# reg_board.net
KiCad netlist of a schematic drawn in EAGLE
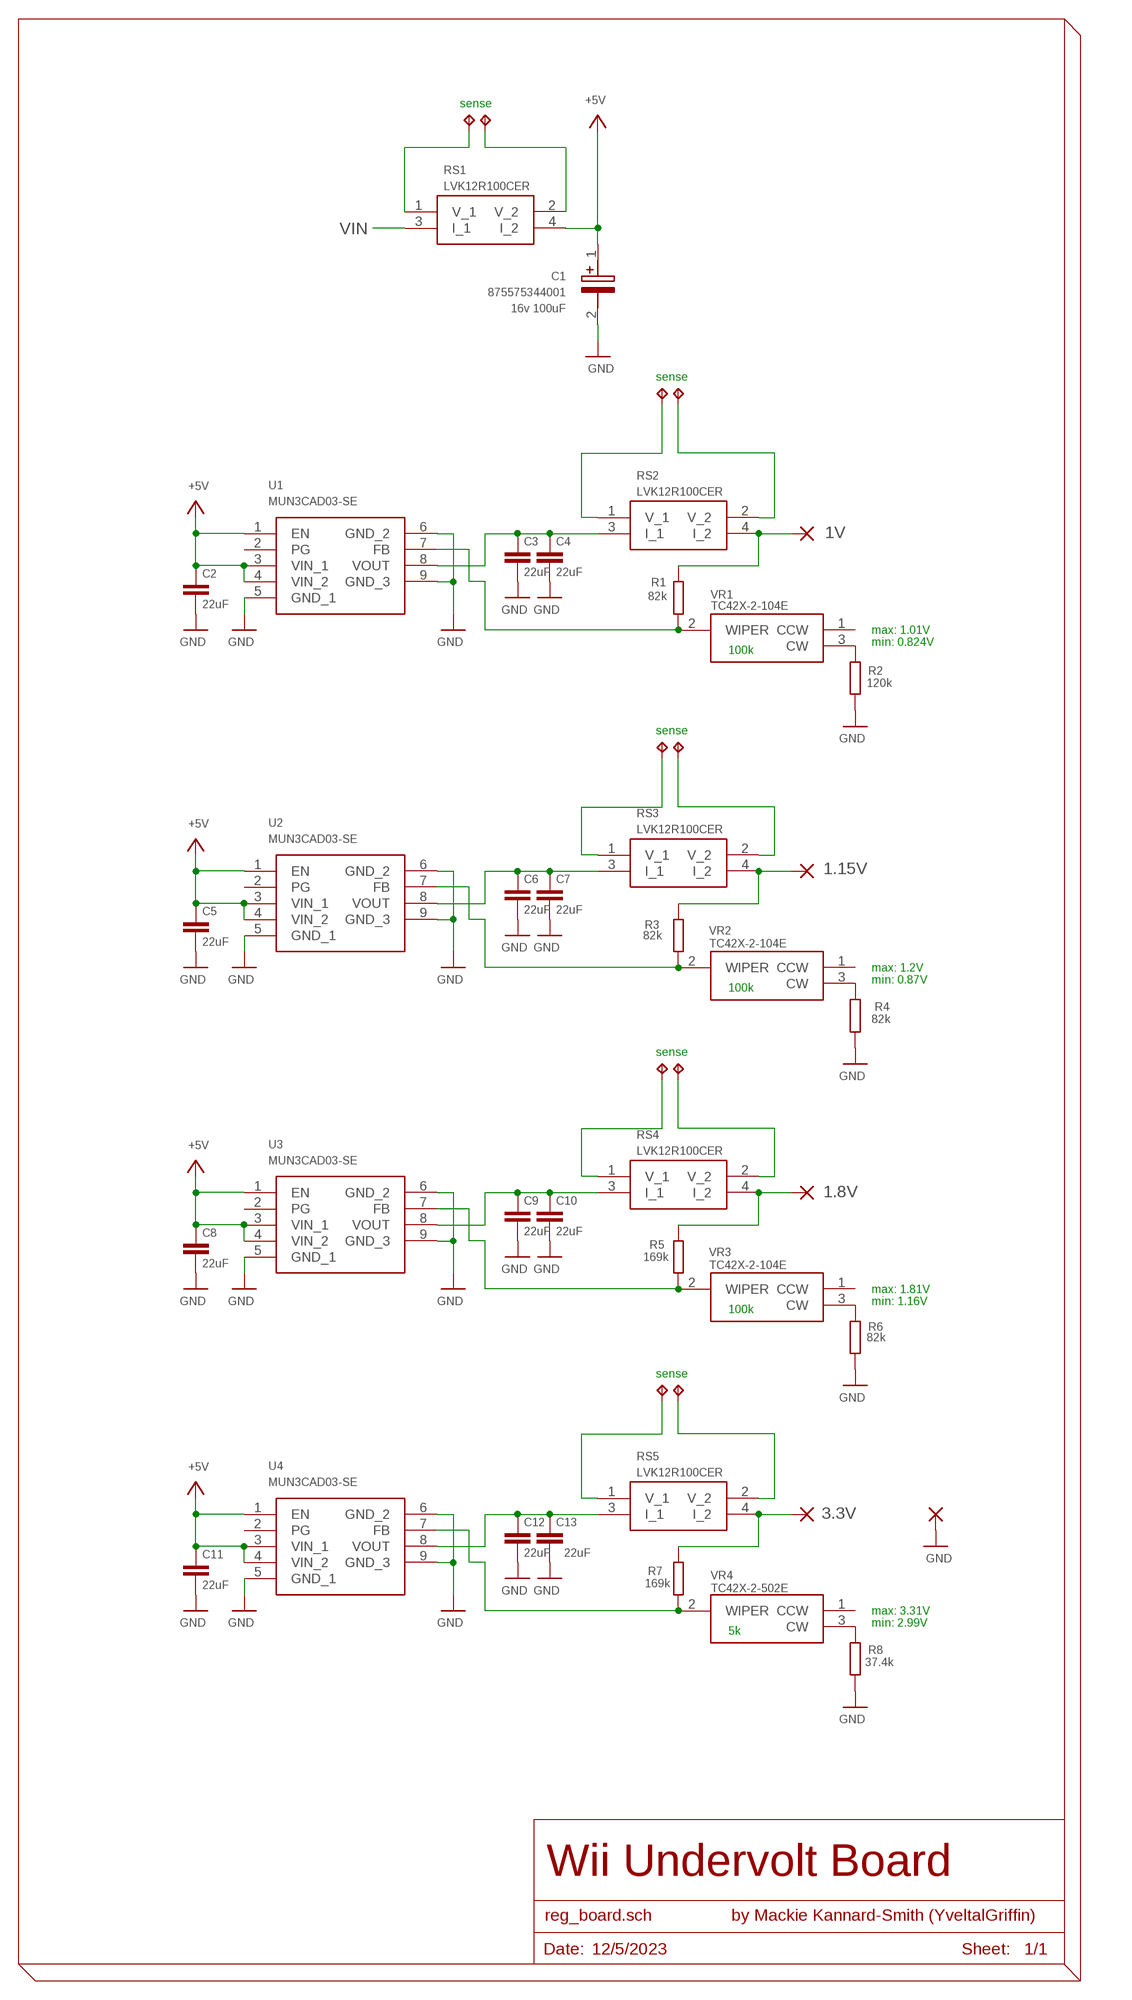
[diagram p0: schematic, sheet 1]

(export (version "E")
  (design (tool "Eeschema 10.0.6"))
  (components
    (comp (ref "C1")
      (value "875575344001")
      (footprint "eagle-import:CAPAE660X610N")
      (libsource (lib "eagle-import") (part "875575344001"))
    )
    (comp (ref "C2")
      (value "22uF")
      (footprint "eagle-import:C0603")
      (libsource (lib "eagle-import") (part "C-USC0603"))
    )
    (comp (ref "C3")
      (value "22uF")
      (footprint "eagle-import:C0603")
      (libsource (lib "eagle-import") (part "C-USC0603"))
    )
    (comp (ref "C4")
      (value "22uF")
      (footprint "eagle-import:C0603")
      (libsource (lib "eagle-import") (part "C-USC0603"))
    )
    (comp (ref "C5")
      (value "22uF")
      (footprint "eagle-import:C0603")
      (libsource (lib "eagle-import") (part "C-USC0603"))
    )
    (comp (ref "C6")
      (value "22uF")
      (footprint "eagle-import:C0603")
      (libsource (lib "eagle-import") (part "C-USC0603"))
    )
    (comp (ref "C7")
      (value "22uF")
      (footprint "eagle-import:C0603")
      (libsource (lib "eagle-import") (part "C-USC0603"))
    )
    (comp (ref "C8")
      (value "22uF")
      (footprint "eagle-import:C0603")
      (libsource (lib "eagle-import") (part "C-USC0603"))
    )
    (comp (ref "C9")
      (value "22uF")
      (footprint "eagle-import:C0603")
      (libsource (lib "eagle-import") (part "C-USC0603"))
    )
    (comp (ref "C10")
      (value "22uF")
      (footprint "eagle-import:C0603")
      (libsource (lib "eagle-import") (part "C-USC0603"))
    )
    (comp (ref "C11")
      (value "22uF")
      (footprint "eagle-import:C0603")
      (libsource (lib "eagle-import") (part "C-USC0603"))
    )
    (comp (ref "C12")
      (value "22uF")
      (footprint "eagle-import:C0603")
      (libsource (lib "eagle-import") (part "C-USC0603"))
    )
    (comp (ref "C13")
      (value "22uF")
      (footprint "eagle-import:C0603")
      (libsource (lib "eagle-import") (part "C-USC0603"))
    )
    (comp (ref "PAD1")
      (value "SMD5")
      (footprint "eagle-import:SMD2,54-5,08")
      (libsource (lib "eagle-import") (part "SMD5"))
    )
    (comp (ref "PAD2")
      (value "SMD5")
      (footprint "eagle-import:SMD2,54-5,08")
      (libsource (lib "eagle-import") (part "SMD5"))
    )
    (comp (ref "PAD3")
      (value "SMD5")
      (footprint "eagle-import:SMD2,54-5,08")
      (libsource (lib "eagle-import") (part "SMD5"))
    )
    (comp (ref "PAD4")
      (value "SMD5")
      (footprint "eagle-import:SMD2,54-5,08")
      (libsource (lib "eagle-import") (part "SMD5"))
    )
    (comp (ref "PAD5")
      (value "SMD5")
      (footprint "eagle-import:SMD2,54-5,08")
      (libsource (lib "eagle-import") (part "SMD5"))
    )
    (comp (ref "R1")
      (value "82k")
      (footprint "eagle-import:R0402")
      (libsource (lib "eagle-import") (part "R-US_R0402"))
    )
    (comp (ref "R2")
      (value "120k")
      (footprint "eagle-import:R0402")
      (libsource (lib "eagle-import") (part "R-US_R0402"))
    )
    (comp (ref "R3")
      (value "82k")
      (footprint "eagle-import:R0402")
      (libsource (lib "eagle-import") (part "R-US_R0402"))
    )
    (comp (ref "R4")
      (value "82k")
      (footprint "eagle-import:R0402")
      (libsource (lib "eagle-import") (part "R-US_R0402"))
    )
    (comp (ref "R5")
      (value "169k")
      (footprint "eagle-import:R0402")
      (libsource (lib "eagle-import") (part "R-US_R0402"))
    )
    (comp (ref "R6")
      (value "82k")
      (footprint "eagle-import:R0402")
      (libsource (lib "eagle-import") (part "R-US_R0402"))
    )
    (comp (ref "R7")
      (value "169k")
      (footprint "eagle-import:R0402")
      (libsource (lib "eagle-import") (part "R-US_R0402"))
    )
    (comp (ref "R8")
      (value "37.4k")
      (footprint "eagle-import:R0402")
      (libsource (lib "eagle-import") (part "R-US_R0402"))
    )
    (comp (ref "RS1")
      (value "LVK12R100CER")
      (footprint "eagle-import:LVK12R100CER")
      (fields (field (name "MOUSER_PART_NUMBER") "588-LVK12R100CER"))
      (libsource (lib "eagle-import") (part "LVK12R100CER"))
    )
    (comp (ref "RS2")
      (value "LVK12R100CER")
      (footprint "eagle-import:LVK12R100CER")
      (fields (field (name "MOUSER_PART_NUMBER") "588-LVK12R100CER"))
      (libsource (lib "eagle-import") (part "LVK12R100CER"))
    )
    (comp (ref "RS3")
      (value "LVK12R100CER")
      (footprint "eagle-import:LVK12R100CER")
      (fields (field (name "MOUSER_PART_NUMBER") "588-LVK12R100CER"))
      (libsource (lib "eagle-import") (part "LVK12R100CER"))
    )
    (comp (ref "RS4")
      (value "LVK12R100CER")
      (footprint "eagle-import:LVK12R100CER")
      (fields (field (name "MOUSER_PART_NUMBER") "588-LVK12R100CER"))
      (libsource (lib "eagle-import") (part "LVK12R100CER"))
    )
    (comp (ref "RS5")
      (value "LVK12R100CER")
      (footprint "eagle-import:LVK12R100CER")
      (fields (field (name "MOUSER_PART_NUMBER") "588-LVK12R100CER"))
      (libsource (lib "eagle-import") (part "LVK12R100CER"))
    )
    (comp (ref "TP1")
      (value "TPTP08R")
      (footprint "eagle-import:TP08R")
      (libsource (lib "eagle-import") (part "TPTP08R"))
    )
    (comp (ref "TP2")
      (value "TPTP08R")
      (footprint "eagle-import:TP08R")
      (libsource (lib "eagle-import") (part "TPTP08R"))
    )
    (comp (ref "TP3")
      (value "TPTP08R")
      (footprint "eagle-import:TP08R")
      (libsource (lib "eagle-import") (part "TPTP08R"))
    )
    (comp (ref "TP4")
      (value "TPTP08R")
      (footprint "eagle-import:TP08R")
      (libsource (lib "eagle-import") (part "TPTP08R"))
    )
    (comp (ref "TP5")
      (value "TPTP08R")
      (footprint "eagle-import:TP08R")
      (libsource (lib "eagle-import") (part "TPTP08R"))
    )
    (comp (ref "TP6")
      (value "TPTP08R")
      (footprint "eagle-import:TP08R")
      (libsource (lib "eagle-import") (part "TPTP08R"))
    )
    (comp (ref "TP7")
      (value "TPTP08R")
      (footprint "eagle-import:TP08R")
      (libsource (lib "eagle-import") (part "TPTP08R"))
    )
    (comp (ref "TP8")
      (value "TPTP08R")
      (footprint "eagle-import:TP08R")
      (libsource (lib "eagle-import") (part "TPTP08R"))
    )
    (comp (ref "TP9")
      (value "TPTP08R")
      (footprint "eagle-import:TP08R")
      (libsource (lib "eagle-import") (part "TPTP08R"))
    )
    (comp (ref "TP10")
      (value "TPTP08R")
      (footprint "eagle-import:TP08R")
      (libsource (lib "eagle-import") (part "TPTP08R"))
    )
    (comp (ref "U1")
      (value "MUN3CAD03-SE")
      (footprint "eagle-import:MUN3CAD03SE")
      (fields (field (name "MOUSER_PART_NUMBER") "108-MUN3CAD03-SE"))
      (libsource (lib "eagle-import") (part "MUN3CAD03-SE"))
    )
    (comp (ref "U2")
      (value "MUN3CAD03-SE")
      (footprint "eagle-import:MUN3CAD03SE")
      (fields (field (name "MOUSER_PART_NUMBER") "108-MUN3CAD03-SE"))
      (libsource (lib "eagle-import") (part "MUN3CAD03-SE"))
    )
    (comp (ref "U3")
      (value "MUN3CAD03-SE")
      (footprint "eagle-import:MUN3CAD03SE")
      (fields (field (name "MOUSER_PART_NUMBER") "108-MUN3CAD03-SE"))
      (libsource (lib "eagle-import") (part "MUN3CAD03-SE"))
    )
    (comp (ref "U4")
      (value "MUN3CAD03-SE")
      (footprint "eagle-import:MUN3CAD03SE")
      (fields (field (name "MOUSER_PART_NUMBER") "108-MUN3CAD03-SE"))
      (libsource (lib "eagle-import") (part "MUN3CAD03-SE"))
    )
    (comp (ref "VR1")
      (value "TC42X-2-104E")
      (footprint "eagle-import:TC42X2103E")
      (fields (field (name "MOUSER_PART_NUMBER") "652-TC42X-2-104E"))
      (libsource (lib "eagle-import") (part "TC42X-2-104E"))
    )
    (comp (ref "VR2")
      (value "TC42X-2-104E")
      (footprint "eagle-import:TC42X2103E")
      (fields (field (name "MOUSER_PART_NUMBER") "652-TC42X-2-104E"))
      (libsource (lib "eagle-import") (part "TC42X-2-104E"))
    )
    (comp (ref "VR3")
      (value "TC42X-2-104E")
      (footprint "eagle-import:TC42X2103E")
      (fields (field (name "MOUSER_PART_NUMBER") "652-TC42X-2-104E"))
      (libsource (lib "eagle-import") (part "TC42X-2-104E"))
    )
    (comp (ref "VR4")
      (value "TC42X-2-502E")
      (footprint "eagle-import:TC42X2103E")
      (fields
        (field (name "MANUFACTURER_PART_NUMBER") "TC42X-2-104E")
        (field (name "MOUSER_PART_NUMBER") "652-TC42X-2-104E")
      )
      (libsource (lib "eagle-import") (part "TC42X-2-104E"))
    )
  )
  (nets
    (net (code "1") (name "+5V") (class "Default")
      (node (ref "C1") (pin "1") (pinfunction "+_1") (pintype "bidirectional"))
      (node (ref "C11") (pin "1") (pinfunction "1_1") (pintype "passive"))
      (node (ref "C2") (pin "1") (pinfunction "1_1") (pintype "passive"))
      (node (ref "C5") (pin "1") (pinfunction "1_1") (pintype "passive"))
      (node (ref "C8") (pin "1") (pinfunction "1_1") (pintype "passive"))
      (node (ref "RS1") (pin "4") (pinfunction "I_2_4") (pintype "bidirectional"))
      (node (ref "U1") (pin "1") (pinfunction "EN_1") (pintype "bidirectional"))
      (node (ref "U1") (pin "3") (pinfunction "VIN_1_3") (pintype "bidirectional"))
      (node (ref "U1") (pin "4") (pinfunction "VIN_2_4") (pintype "bidirectional"))
      (node (ref "U2") (pin "1") (pinfunction "EN_1") (pintype "bidirectional"))
      (node (ref "U2") (pin "3") (pinfunction "VIN_1_3") (pintype "bidirectional"))
      (node (ref "U2") (pin "4") (pinfunction "VIN_2_4") (pintype "bidirectional"))
      (node (ref "U3") (pin "1") (pinfunction "EN_1") (pintype "bidirectional"))
      (node (ref "U3") (pin "3") (pinfunction "VIN_1_3") (pintype "bidirectional"))
      (node (ref "U3") (pin "4") (pinfunction "VIN_2_4") (pintype "bidirectional"))
      (node (ref "U4") (pin "1") (pinfunction "EN_1") (pintype "bidirectional"))
      (node (ref "U4") (pin "3") (pinfunction "VIN_1_3") (pintype "bidirectional"))
      (node (ref "U4") (pin "4") (pinfunction "VIN_2_4") (pintype "bidirectional"))
    )
    (net (code "2") (name "/1.8V") (class "Default")
      (node (ref "PAD4") (pin "1") (pinfunction "P_1") (pintype "passive"))
      (node (ref "R5") (pin "2") (pinfunction "2_2") (pintype "passive"))
      (node (ref "RS4") (pin "4") (pinfunction "I_2_4") (pintype "bidirectional"))
    )
    (net (code "3") (name "/1.15V") (class "Default")
      (node (ref "PAD3") (pin "1") (pinfunction "P_1") (pintype "passive"))
      (node (ref "R3") (pin "2") (pinfunction "2_2") (pintype "passive"))
      (node (ref "RS3") (pin "4") (pinfunction "I_2_4") (pintype "bidirectional"))
    )
    (net (code "4") (name "/1V") (class "Default")
      (node (ref "PAD1") (pin "1") (pinfunction "P_1") (pintype "passive"))
      (node (ref "R1") (pin "2") (pinfunction "2_2") (pintype "passive"))
      (node (ref "RS2") (pin "4") (pinfunction "I_2_4") (pintype "bidirectional"))
    )
    (net (code "5") (name "/3.3V") (class "Default")
      (node (ref "PAD5") (pin "1") (pinfunction "P_1") (pintype "passive"))
      (node (ref "R7") (pin "2") (pinfunction "2_2") (pintype "passive"))
      (node (ref "RS5") (pin "4") (pinfunction "I_2_4") (pintype "bidirectional"))
    )
    (net (code "6") (name "/VIN") (class "Default")
      (node (ref "RS1") (pin "3") (pinfunction "I_1_3") (pintype "bidirectional"))
    )
    (net (code "7") (name "GND") (class "Default")
      (node (ref "C1") (pin "2") (pinfunction "-_2") (pintype "bidirectional"))
      (node (ref "C10") (pin "2") (pinfunction "2_2") (pintype "passive"))
      (node (ref "C11") (pin "2") (pinfunction "2_2") (pintype "passive"))
      (node (ref "C12") (pin "2") (pinfunction "2_2") (pintype "passive"))
      (node (ref "C13") (pin "2") (pinfunction "2_2") (pintype "passive"))
      (node (ref "C2") (pin "2") (pinfunction "2_2") (pintype "passive"))
      (node (ref "C3") (pin "2") (pinfunction "2_2") (pintype "passive"))
      (node (ref "C4") (pin "2") (pinfunction "2_2") (pintype "passive"))
      (node (ref "C5") (pin "2") (pinfunction "2_2") (pintype "passive"))
      (node (ref "C6") (pin "2") (pinfunction "2_2") (pintype "passive"))
      (node (ref "C7") (pin "2") (pinfunction "2_2") (pintype "passive"))
      (node (ref "C8") (pin "2") (pinfunction "2_2") (pintype "passive"))
      (node (ref "C9") (pin "2") (pinfunction "2_2") (pintype "passive"))
      (node (ref "PAD2") (pin "1") (pinfunction "P_1") (pintype "passive"))
      (node (ref "R2") (pin "1") (pinfunction "1_1") (pintype "passive"))
      (node (ref "R4") (pin "1") (pinfunction "1_1") (pintype "passive"))
      (node (ref "R6") (pin "1") (pinfunction "1_1") (pintype "passive"))
      (node (ref "R8") (pin "1") (pinfunction "1_1") (pintype "passive"))
      (node (ref "U1") (pin "5") (pinfunction "GND_1_5") (pintype "bidirectional"))
      (node (ref "U1") (pin "6") (pinfunction "GND_2_6") (pintype "bidirectional"))
      (node (ref "U1") (pin "9") (pinfunction "GND_3_9") (pintype "bidirectional"))
      (node (ref "U2") (pin "5") (pinfunction "GND_1_5") (pintype "bidirectional"))
      (node (ref "U2") (pin "6") (pinfunction "GND_2_6") (pintype "bidirectional"))
      (node (ref "U2") (pin "9") (pinfunction "GND_3_9") (pintype "bidirectional"))
      (node (ref "U3") (pin "5") (pinfunction "GND_1_5") (pintype "bidirectional"))
      (node (ref "U3") (pin "6") (pinfunction "GND_2_6") (pintype "bidirectional"))
      (node (ref "U3") (pin "9") (pinfunction "GND_3_9") (pintype "bidirectional"))
      (node (ref "U4") (pin "5") (pinfunction "GND_1_5") (pintype "bidirectional"))
      (node (ref "U4") (pin "6") (pinfunction "GND_2_6") (pintype "bidirectional"))
      (node (ref "U4") (pin "9") (pinfunction "GND_3_9") (pintype "bidirectional"))
    )
    (net (code "8") (name "Net-(RS1-V_1)") (class "Default")
      (node (ref "RS1") (pin "1") (pinfunction "V_1_1") (pintype "bidirectional"))
      (node (ref "TP4") (pin "TP") (pinfunction "TP_TP") (pintype "input"))
    )
    (net (code "9") (name "Net-(RS1-V_2)") (class "Default")
      (node (ref "RS1") (pin "2") (pinfunction "V_2_2") (pintype "bidirectional"))
      (node (ref "TP3") (pin "TP") (pinfunction "TP_TP") (pintype "input"))
    )
    (net (code "10") (name "Net-(RS2-I_1)") (class "Default")
      (node (ref "C3") (pin "1") (pinfunction "1_1") (pintype "passive"))
      (node (ref "C4") (pin "1") (pinfunction "1_1") (pintype "passive"))
      (node (ref "RS2") (pin "3") (pinfunction "I_1_3") (pintype "bidirectional"))
      (node (ref "U1") (pin "8") (pinfunction "VOUT_8") (pintype "bidirectional"))
    )
    (net (code "11") (name "Net-(RS2-V_1)") (class "Default")
      (node (ref "RS2") (pin "1") (pinfunction "V_1_1") (pintype "bidirectional"))
      (node (ref "TP1") (pin "TP") (pinfunction "TP_TP") (pintype "input"))
    )
    (net (code "12") (name "Net-(RS2-V_2)") (class "Default")
      (node (ref "RS2") (pin "2") (pinfunction "V_2_2") (pintype "bidirectional"))
      (node (ref "TP2") (pin "TP") (pinfunction "TP_TP") (pintype "input"))
    )
    (net (code "13") (name "Net-(RS3-I_1)") (class "Default")
      (node (ref "C6") (pin "1") (pinfunction "1_1") (pintype "passive"))
      (node (ref "C7") (pin "1") (pinfunction "1_1") (pintype "passive"))
      (node (ref "RS3") (pin "3") (pinfunction "I_1_3") (pintype "bidirectional"))
      (node (ref "U2") (pin "8") (pinfunction "VOUT_8") (pintype "bidirectional"))
    )
    (net (code "14") (name "Net-(RS3-V_1)") (class "Default")
      (node (ref "RS3") (pin "1") (pinfunction "V_1_1") (pintype "bidirectional"))
      (node (ref "TP5") (pin "TP") (pinfunction "TP_TP") (pintype "input"))
    )
    (net (code "15") (name "Net-(RS3-V_2)") (class "Default")
      (node (ref "RS3") (pin "2") (pinfunction "V_2_2") (pintype "bidirectional"))
      (node (ref "TP6") (pin "TP") (pinfunction "TP_TP") (pintype "input"))
    )
    (net (code "16") (name "Net-(RS4-I_1)") (class "Default")
      (node (ref "C10") (pin "1") (pinfunction "1_1") (pintype "passive"))
      (node (ref "C9") (pin "1") (pinfunction "1_1") (pintype "passive"))
      (node (ref "RS4") (pin "3") (pinfunction "I_1_3") (pintype "bidirectional"))
      (node (ref "U3") (pin "8") (pinfunction "VOUT_8") (pintype "bidirectional"))
    )
    (net (code "17") (name "Net-(RS4-V_1)") (class "Default")
      (node (ref "RS4") (pin "1") (pinfunction "V_1_1") (pintype "bidirectional"))
      (node (ref "TP7") (pin "TP") (pinfunction "TP_TP") (pintype "input"))
    )
    (net (code "18") (name "Net-(RS4-V_2)") (class "Default")
      (node (ref "RS4") (pin "2") (pinfunction "V_2_2") (pintype "bidirectional"))
      (node (ref "TP8") (pin "TP") (pinfunction "TP_TP") (pintype "input"))
    )
    (net (code "19") (name "Net-(RS5-I_1)") (class "Default")
      (node (ref "C12") (pin "1") (pinfunction "1_1") (pintype "passive"))
      (node (ref "C13") (pin "1") (pinfunction "1_1") (pintype "passive"))
      (node (ref "RS5") (pin "3") (pinfunction "I_1_3") (pintype "bidirectional"))
      (node (ref "U4") (pin "8") (pinfunction "VOUT_8") (pintype "bidirectional"))
    )
    (net (code "20") (name "Net-(RS5-V_1)") (class "Default")
      (node (ref "RS5") (pin "1") (pinfunction "V_1_1") (pintype "bidirectional"))
      (node (ref "TP9") (pin "TP") (pinfunction "TP_TP") (pintype "input"))
    )
    (net (code "21") (name "Net-(RS5-V_2)") (class "Default")
      (node (ref "RS5") (pin "2") (pinfunction "V_2_2") (pintype "bidirectional"))
      (node (ref "TP10") (pin "TP") (pinfunction "TP_TP") (pintype "input"))
    )
    (net (code "22") (name "Net-(U1-FB)") (class "Default")
      (node (ref "R1") (pin "1") (pinfunction "1_1") (pintype "passive"))
      (node (ref "U1") (pin "7") (pinfunction "FB_7") (pintype "bidirectional"))
      (node (ref "VR1") (pin "2") (pinfunction "WIPER_2") (pintype "bidirectional"))
    )
    (net (code "23") (name "Net-(U2-FB)") (class "Default")
      (node (ref "R3") (pin "1") (pinfunction "1_1") (pintype "passive"))
      (node (ref "U2") (pin "7") (pinfunction "FB_7") (pintype "bidirectional"))
      (node (ref "VR2") (pin "2") (pinfunction "WIPER_2") (pintype "bidirectional"))
    )
    (net (code "24") (name "Net-(U3-FB)") (class "Default")
      (node (ref "R5") (pin "1") (pinfunction "1_1") (pintype "passive"))
      (node (ref "U3") (pin "7") (pinfunction "FB_7") (pintype "bidirectional"))
      (node (ref "VR3") (pin "2") (pinfunction "WIPER_2") (pintype "bidirectional"))
    )
    (net (code "25") (name "Net-(U4-FB)") (class "Default")
      (node (ref "R7") (pin "1") (pinfunction "1_1") (pintype "passive"))
      (node (ref "U4") (pin "7") (pinfunction "FB_7") (pintype "bidirectional"))
      (node (ref "VR4") (pin "2") (pinfunction "WIPER_2") (pintype "bidirectional"))
    )
    (net (code "26") (name "Net-(VR1-CW)") (class "Default")
      (node (ref "R2") (pin "2") (pinfunction "2_2") (pintype "passive"))
      (node (ref "VR1") (pin "3") (pinfunction "CW_3") (pintype "bidirectional"))
    )
    (net (code "27") (name "Net-(VR2-CW)") (class "Default")
      (node (ref "R4") (pin "2") (pinfunction "2_2") (pintype "passive"))
      (node (ref "VR2") (pin "3") (pinfunction "CW_3") (pintype "bidirectional"))
    )
    (net (code "28") (name "Net-(VR3-CW)") (class "Default")
      (node (ref "R6") (pin "2") (pinfunction "2_2") (pintype "passive"))
      (node (ref "VR3") (pin "3") (pinfunction "CW_3") (pintype "bidirectional"))
    )
    (net (code "29") (name "Net-(VR4-CW)") (class "Default")
      (node (ref "R8") (pin "2") (pinfunction "2_2") (pintype "passive"))
      (node (ref "VR4") (pin "3") (pinfunction "CW_3") (pintype "bidirectional"))
    )
    (net (code "30") (name "unconnected-(U1-PG-Pad2)") (class "Default")
      (node (ref "U1") (pin "2") (pinfunction "PG_2") (pintype "bidirectional"))
    )
    (net (code "31") (name "unconnected-(U2-PG-Pad2)") (class "Default")
      (node (ref "U2") (pin "2") (pinfunction "PG_2") (pintype "bidirectional"))
    )
    (net (code "32") (name "unconnected-(U3-PG-Pad2)") (class "Default")
      (node (ref "U3") (pin "2") (pinfunction "PG_2") (pintype "bidirectional"))
    )
    (net (code "33") (name "unconnected-(U4-PG-Pad2)") (class "Default")
      (node (ref "U4") (pin "2") (pinfunction "PG_2") (pintype "bidirectional"))
    )
    (net (code "34") (name "unconnected-(VR1-CCW-Pad1)") (class "Default")
      (node (ref "VR1") (pin "1") (pinfunction "CCW_1") (pintype "bidirectional"))
    )
    (net (code "35") (name "unconnected-(VR2-CCW-Pad1)") (class "Default")
      (node (ref "VR2") (pin "1") (pinfunction "CCW_1") (pintype "bidirectional"))
    )
    (net (code "36") (name "unconnected-(VR3-CCW-Pad1)") (class "Default")
      (node (ref "VR3") (pin "1") (pinfunction "CCW_1") (pintype "bidirectional"))
    )
    (net (code "37") (name "unconnected-(VR4-CCW-Pad1)") (class "Default")
      (node (ref "VR4") (pin "1") (pinfunction "CCW_1") (pintype "bidirectional"))
    )
  )
)
